# old_line_kick.net
KiCad netlist of a schematic drawn in EAGLE
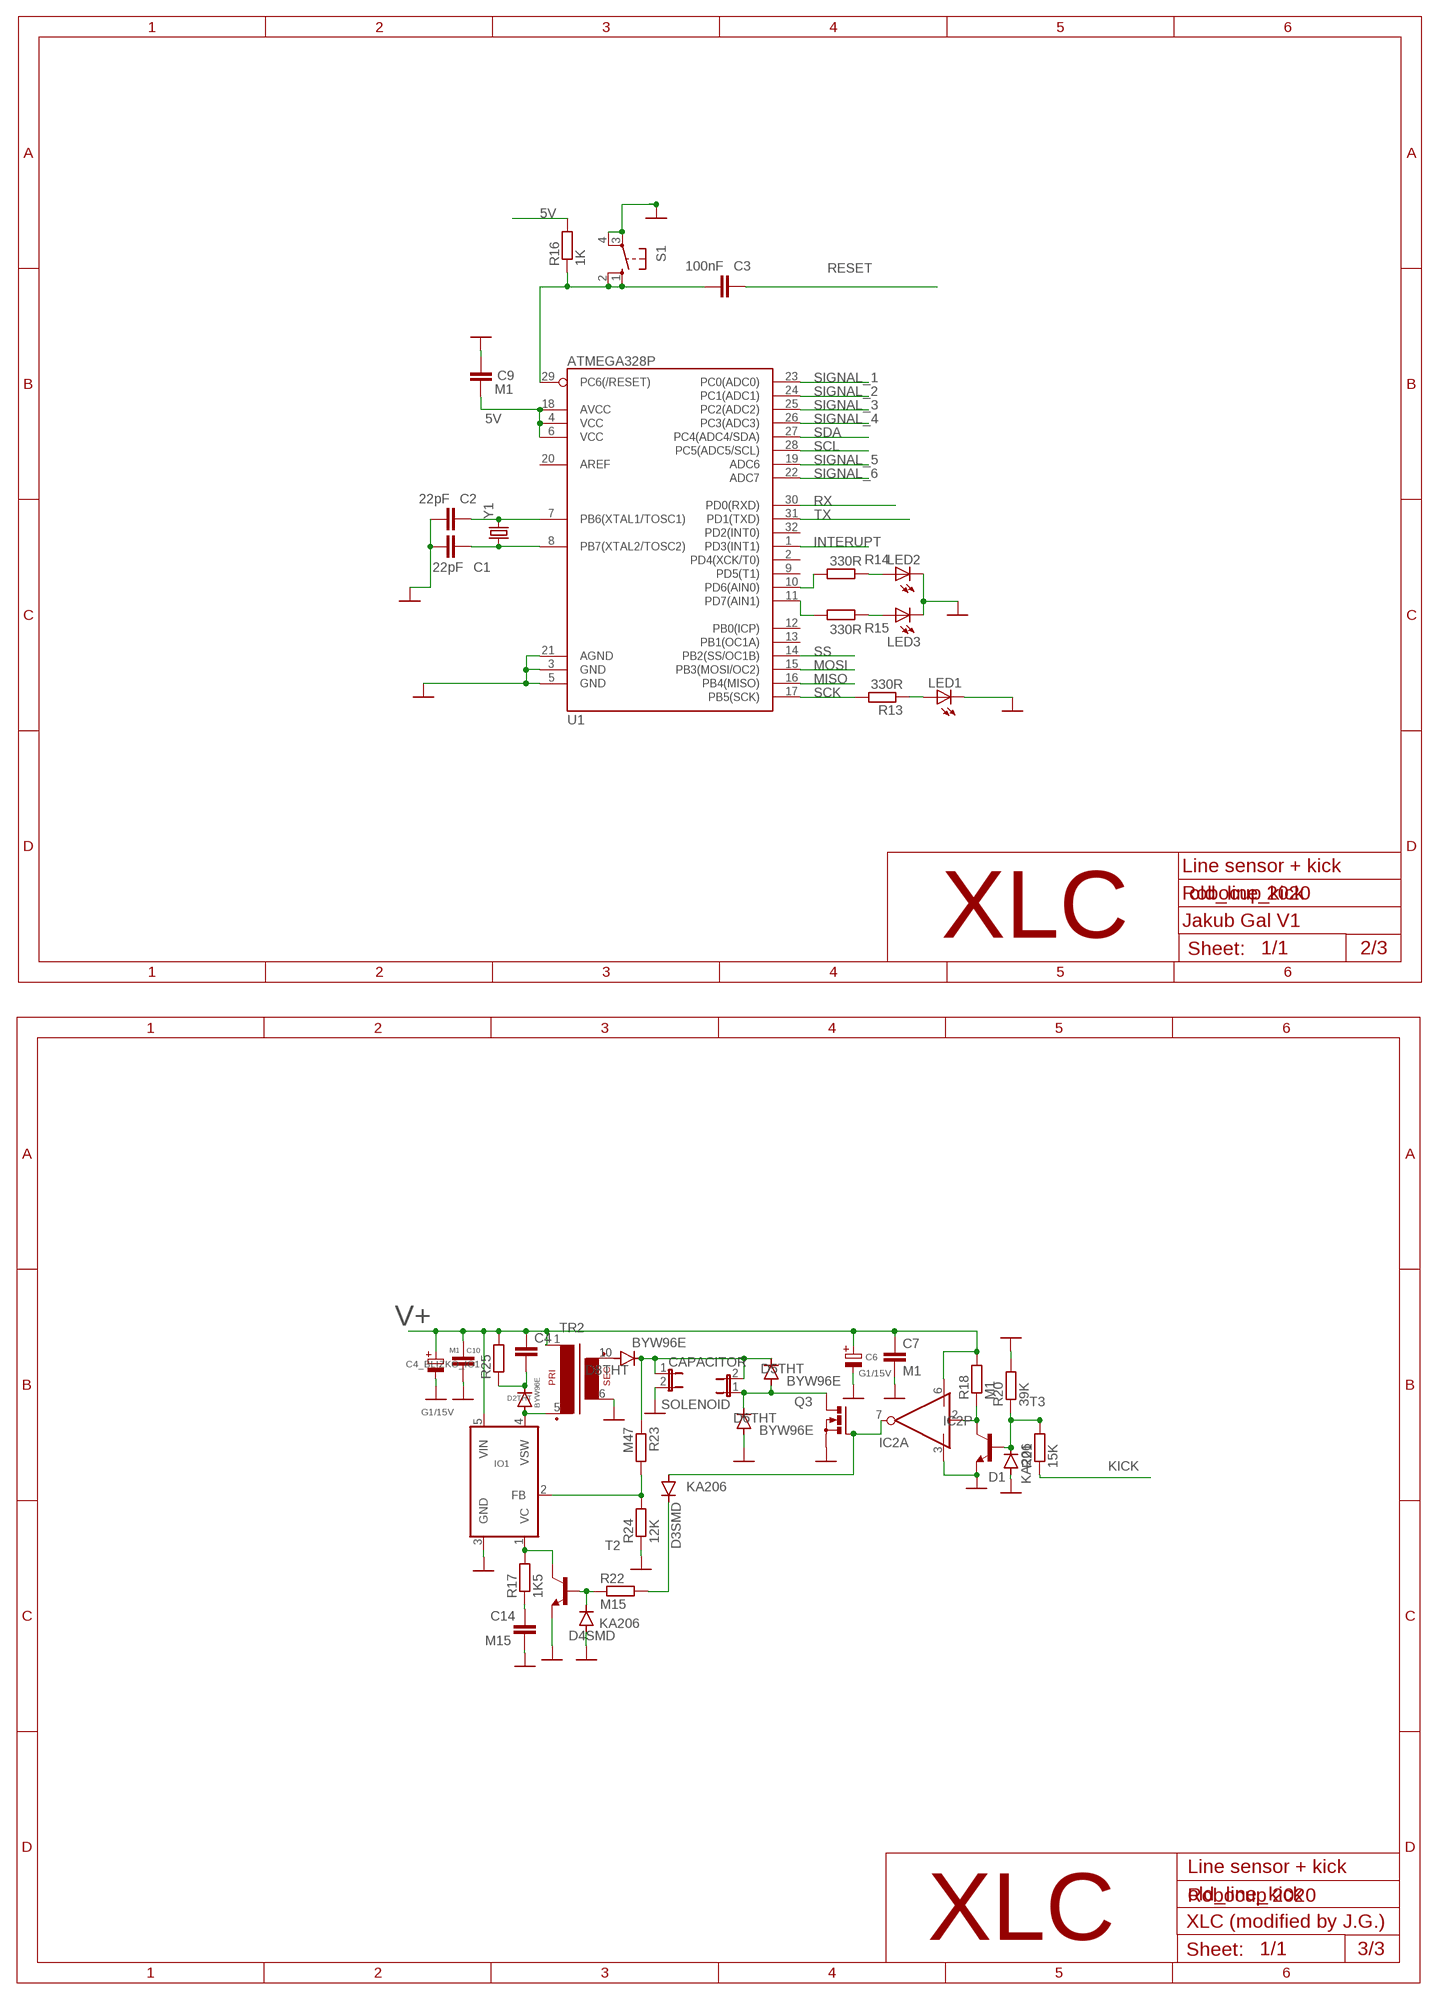
[diagram p0: schematic, sheet 1, part 1 of 2]
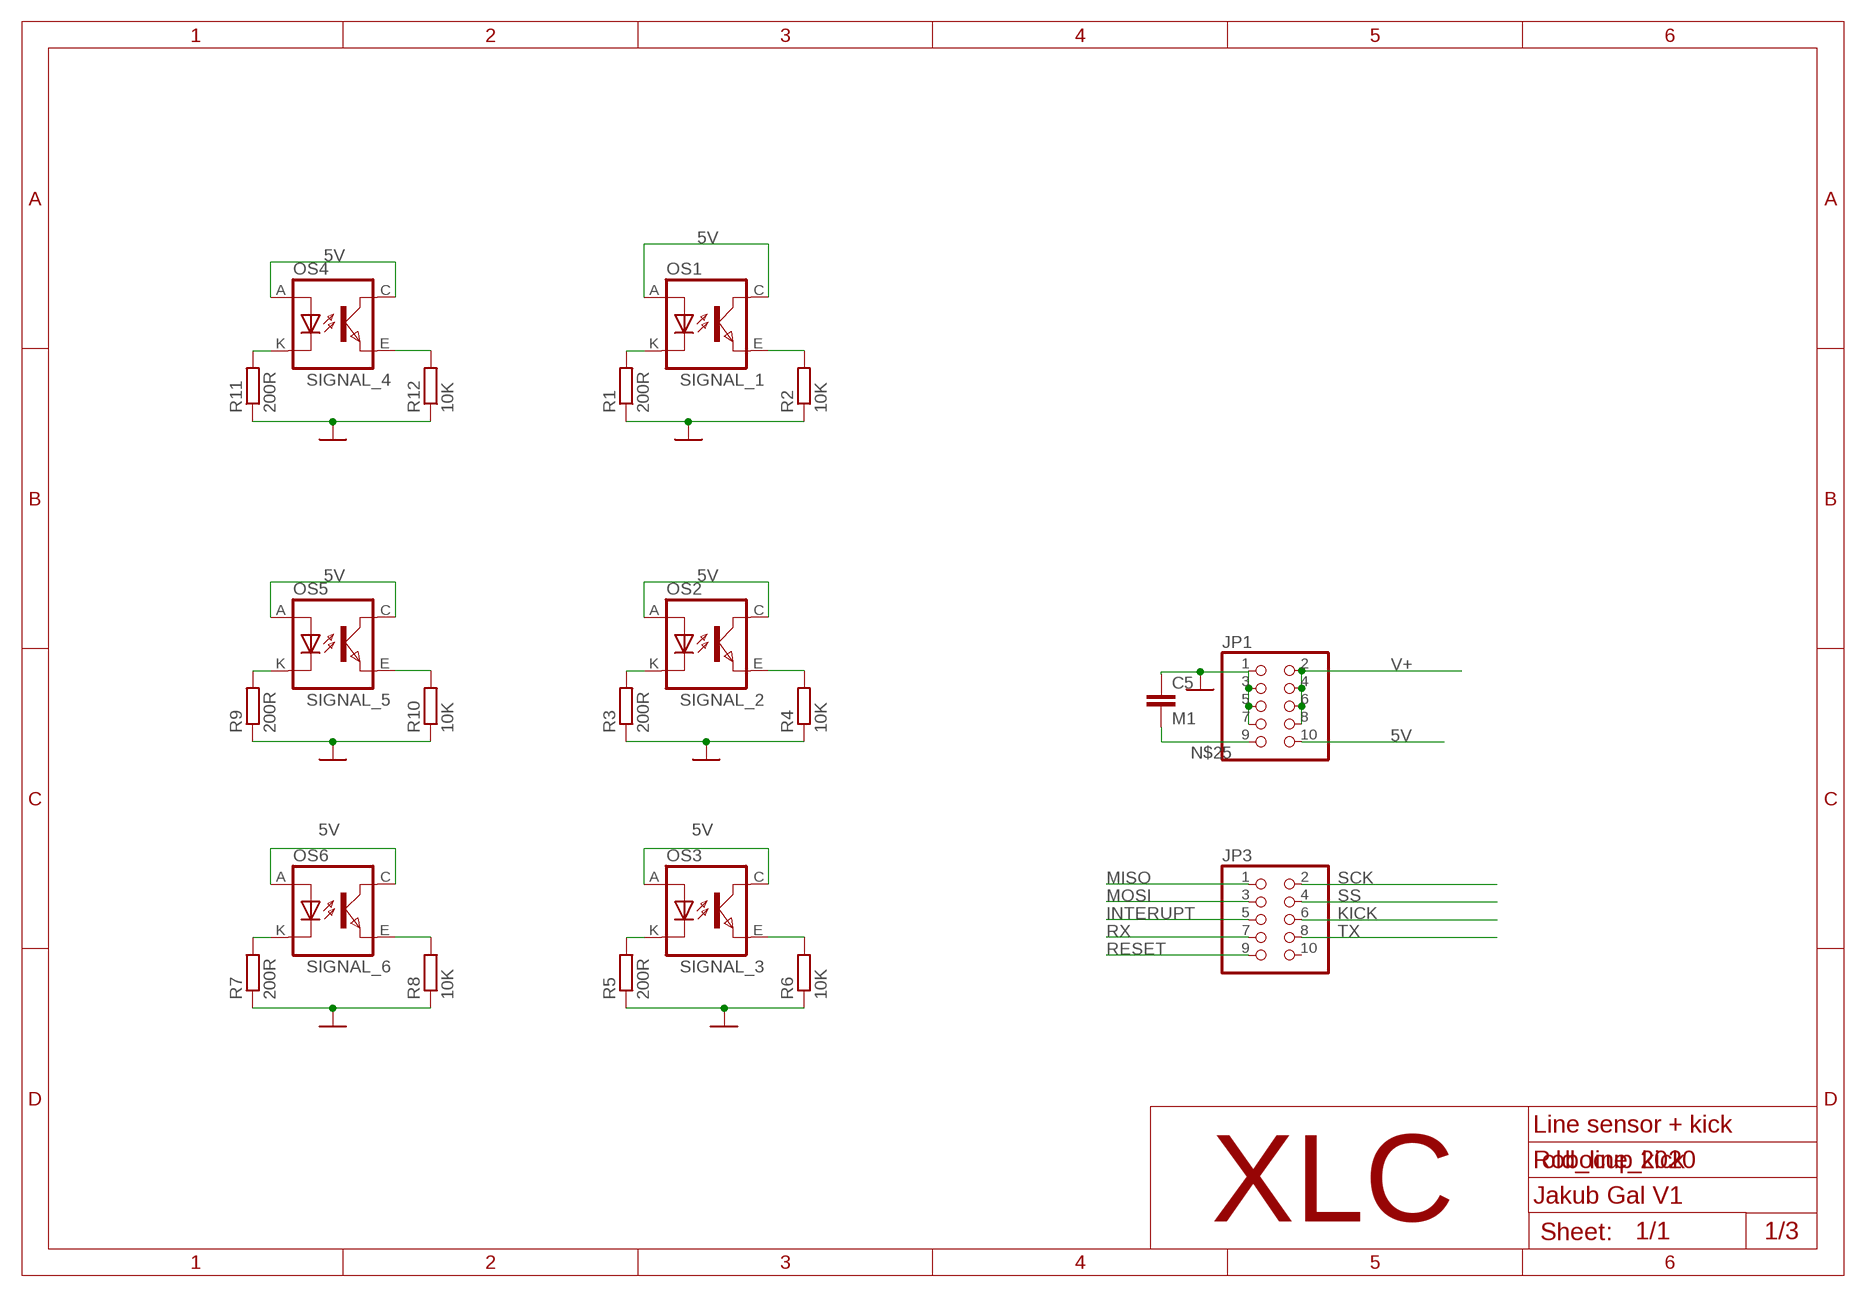
[diagram p1: schematic, sheet 1, part 2 of 2]

(export (version "E")
  (design (tool "Eeschema 10.0.6"))
  (components
    (comp (ref "C1")
      (value "22pF")
      (footprint "eagle-import:C0603")
      (libsource (lib "eagle-import") (part "rcl@1_C-EUC0603"))
    )
    (comp (ref "C2")
      (value "22pF")
      (footprint "eagle-import:C0603")
      (libsource (lib "eagle-import") (part "rcl@1_C-EUC0603"))
    )
    (comp (ref "C3")
      (value "100nF")
      (footprint "eagle-import:C0603")
      (libsource (lib "eagle-import") (part "rcl@1_C-EUC0603"))
    )
    (comp (ref "C4")
      (value "C-EU075-052X106")
      (footprint "eagle-import:C075-052X106")
      (libsource (lib "eagle-import") (part "C-EU075-052X106"))
    )
    (comp (ref "C4_BLIZKO_IO1")
      (value "G1/15V")
      (footprint "eagle-import:E-2,5_7-RAD")
      (libsource (lib "eagle-import") (part "KOND-ELEKT-2,5/7"))
    )
    (comp (ref "C5")
      (value "M1")
      (footprint "eagle-import:C0603")
      (libsource (lib "eagle-import") (part "C-EUC0603"))
    )
    (comp (ref "C6")
      (value "G1/15V")
      (footprint "eagle-import:E-2,5_7-RAD")
      (libsource (lib "eagle-import") (part "KOND-ELEKT-2,5/7"))
    )
    (comp (ref "C7")
      (value "M1")
      (footprint "eagle-import:C0805K")
      (libsource (lib "eagle-import") (part "resistor_C-EUC0805K"))
    )
    (comp (ref "C9")
      (value "M1")
      (footprint "eagle-import:C0603")
      (libsource (lib "eagle-import") (part "rcl@1_C-EUC0603"))
    )
    (comp (ref "C10")
      (value "M1")
      (footprint "eagle-import:C0805K")
      (libsource (lib "eagle-import") (part "resistor_C-EUC0805K"))
    )
    (comp (ref "C14")
      (value "M15")
      (footprint "eagle-import:C0805K")
      (libsource (lib "eagle-import") (part "resistor_C-EUC0805K"))
    )
    (comp (ref "CAPACITOR")
      (value "JP1E")
      (footprint "eagle-import:JP1")
      (libsource (lib "eagle-import") (part "JP1E"))
    )
    (comp (ref "D1")
      (value "KA206")
      (footprint "eagle-import:D-7.5")
      (libsource (lib "eagle-import") (part "DIODE-D-7.5"))
    )
    (comp (ref "D2THT")
      (value "BYW96E")
      (footprint "eagle-import:SOD64-10")
      (libsource (lib "eagle-import") (part "BYW96"))
    )
    (comp (ref "D3SMD")
      (value "KA206")
      (footprint "eagle-import:D-7.5")
      (libsource (lib "eagle-import") (part "DIODE-D-7.5"))
    )
    (comp (ref "D4SMD")
      (value "KA206")
      (footprint "eagle-import:D-7.5")
      (libsource (lib "eagle-import") (part "DIODE-D-7.5"))
    )
    (comp (ref "D5THT")
      (value "BYW96E")
      (footprint "eagle-import:SOD64-10")
      (libsource (lib "eagle-import") (part "BYW96"))
    )
    (comp (ref "D6THT")
      (value "BYW96E")
      (footprint "eagle-import:SOD64-10")
      (libsource (lib "eagle-import") (part "BYW96"))
    )
    (comp (ref "D8THT")
      (value "BYW96E")
      (footprint "eagle-import:SOD64-10")
      (libsource (lib "eagle-import") (part "BYW96"))
    )
    (comp (ref "IC2")
      (value "MIC4423BM")
      (footprint "eagle-import:SO08")
      (libsource (lib "eagle-import") (part "MIC4423BM"))
    )
    (comp (ref "IO1")
      (value "LT1071V")
      (footprint "eagle-import:TO220-5P")
      (libsource (lib "eagle-import") (part "LT1071V"))
    )
    (comp (ref "JP1")
      (value "PINHD-2X5IDC")
      (footprint "eagle-import:2X05_IDC")
      (libsource (lib "eagle-import") (part "PINHD-2X5IDC"))
    )
    (comp (ref "JP3")
      (value "PINHD-2X5IDC")
      (footprint "eagle-import:2X05_IDC")
      (libsource (lib "eagle-import") (part "PINHD-2X5IDC"))
    )
    (comp (ref "LED1")
      (value "LEDCHIPLED_0603")
      (footprint "eagle-import:CHIPLED_0603")
      (libsource (lib "eagle-import") (part "LEDCHIPLED_0603"))
    )
    (comp (ref "LED2")
      (value "LEDCHIPLED_0603")
      (footprint "eagle-import:CHIPLED_0603")
      (libsource (lib "eagle-import") (part "LEDCHIPLED_0603"))
    )
    (comp (ref "LED3")
      (value "LEDCHIPLED_0603")
      (footprint "eagle-import:CHIPLED_0603")
      (libsource (lib "eagle-import") (part "LEDCHIPLED_0603"))
    )
    (comp (ref "OS1")
      (value "TCRT5000")
      (footprint "eagle-import:TCRT5000")
      (libsource (lib "eagle-import") (part "TCRT5000"))
    )
    (comp (ref "OS2")
      (value "TCRT5000")
      (footprint "eagle-import:TCRT5000")
      (libsource (lib "eagle-import") (part "TCRT5000"))
    )
    (comp (ref "OS3")
      (value "TCRT5000")
      (footprint "eagle-import:TCRT5000")
      (libsource (lib "eagle-import") (part "TCRT5000"))
    )
    (comp (ref "OS4")
      (value "TCRT5000")
      (footprint "eagle-import:TCRT5000")
      (fields (field (name "SPICEPREFIX") "O"))
      (libsource (lib "eagle-import") (part "TCRT5000"))
    )
    (comp (ref "OS5")
      (value "TCRT5000")
      (footprint "eagle-import:TCRT5000")
      (libsource (lib "eagle-import") (part "TCRT5000"))
    )
    (comp (ref "OS6")
      (value "TCRT5000")
      (footprint "eagle-import:TCRT5000")
      (fields (field (name "SPICEPREFIX") "O"))
      (libsource (lib "eagle-import") (part "TCRT5000"))
    )
    (comp (ref "Q3")
      (value "PMOSFET_NTO220BV")
      (footprint "eagle-import:TO220BV")
      (libsource (lib "eagle-import") (part "PMOSFET_NTO220BV"))
    )
    (comp (ref "R1")
      (value "200R")
      (footprint "eagle-import:R0603")
      (libsource (lib "eagle-import") (part "R-EU_R0603"))
    )
    (comp (ref "R2")
      (value "10K")
      (footprint "eagle-import:R0603")
      (libsource (lib "eagle-import") (part "R-EU_R0603"))
    )
    (comp (ref "R3")
      (value "200R")
      (footprint "eagle-import:R0603")
      (libsource (lib "eagle-import") (part "R-EU_R0603"))
    )
    (comp (ref "R4")
      (value "10K")
      (footprint "eagle-import:R0603")
      (libsource (lib "eagle-import") (part "R-EU_R0603"))
    )
    (comp (ref "R5")
      (value "200R")
      (footprint "eagle-import:R0603")
      (libsource (lib "eagle-import") (part "R-EU_R0603"))
    )
    (comp (ref "R6")
      (value "10K")
      (footprint "eagle-import:R0603")
      (libsource (lib "eagle-import") (part "R-EU_R0603"))
    )
    (comp (ref "R7")
      (value "200R")
      (footprint "eagle-import:R0603")
      (libsource (lib "eagle-import") (part "R-EU_R0603"))
    )
    (comp (ref "R8")
      (value "10K")
      (footprint "eagle-import:R0603")
      (libsource (lib "eagle-import") (part "R-EU_R0603"))
    )
    (comp (ref "R9")
      (value "200R")
      (footprint "eagle-import:R0603")
      (libsource (lib "eagle-import") (part "R-EU_R0603"))
    )
    (comp (ref "R10")
      (value "10K")
      (footprint "eagle-import:R0603")
      (libsource (lib "eagle-import") (part "R-EU_R0603"))
    )
    (comp (ref "R11")
      (value "200R")
      (footprint "eagle-import:R0603")
      (libsource (lib "eagle-import") (part "R-EU_R0603"))
    )
    (comp (ref "R12")
      (value "10K")
      (footprint "eagle-import:R0603")
      (libsource (lib "eagle-import") (part "R-EU_R0603"))
    )
    (comp (ref "R13")
      (value "330R")
      (footprint "eagle-import:R0603")
      (libsource (lib "eagle-import") (part "R-EU_R0603"))
    )
    (comp (ref "R14")
      (value "330R")
      (footprint "eagle-import:R0603")
      (libsource (lib "eagle-import") (part "R-EU_R0603"))
    )
    (comp (ref "R15")
      (value "330R")
      (footprint "eagle-import:R0603")
      (libsource (lib "eagle-import") (part "R-EU_R0603"))
    )
    (comp (ref "R16")
      (value "1K")
      (footprint "eagle-import:R0603")
      (libsource (lib "eagle-import") (part "R-EU_R0603"))
    )
    (comp (ref "R17")
      (value "1K5")
      (footprint "eagle-import:R1206")
      (libsource (lib "eagle-import") (part "R-EU_R1206"))
    )
    (comp (ref "R18")
      (value "M1")
      (footprint "eagle-import:R1206")
      (libsource (lib "eagle-import") (part "R-EU_R1206"))
    )
    (comp (ref "R20")
      (value "39K")
      (footprint "eagle-import:R1206")
      (libsource (lib "eagle-import") (part "R-EU_R1206"))
    )
    (comp (ref "R21")
      (value "15K")
      (footprint "eagle-import:R1206")
      (libsource (lib "eagle-import") (part "R-EU_R1206"))
    )
    (comp (ref "R22")
      (value "M15")
      (footprint "eagle-import:R1206")
      (libsource (lib "eagle-import") (part "R-EU_R1206"))
    )
    (comp (ref "R23")
      (value "M47")
      (footprint "eagle-import:R1206")
      (libsource (lib "eagle-import") (part "R-EU_R1206"))
    )
    (comp (ref "R24")
      (value "12K")
      (footprint "eagle-import:R1206")
      (libsource (lib "eagle-import") (part "R-EU_R1206"))
    )
    (comp (ref "R25")
      (value "REZISTOR-7,5MM-HORIZ")
      (footprint "eagle-import:R-7,5H")
      (libsource (lib "eagle-import") (part "REZISTOR-7,5MM-HORIZ"))
    )
    (comp (ref "S1")
      (value "10-XX")
      (footprint "eagle-import:B3F-10XX")
      (fields (field (name "MPN") "B3F-1000"))
      (libsource (lib "eagle-import") (part "10-XX"))
    )
    (comp (ref "SOLENOID")
      (value "JP1E")
      (footprint "eagle-import:JP1")
      (libsource (lib "eagle-import") (part "JP1E"))
    )
    (comp (ref "T2")
      (value "-NPN-SC59-BEC")
      (footprint "eagle-import:SC59-BEC")
      (libsource (lib "eagle-import") (part "-NPN-SC59-BEC"))
    )
    (comp (ref "T3")
      (value "-NPN-SC59-BEC")
      (footprint "eagle-import:SC59-BEC")
      (libsource (lib "eagle-import") (part "-NPN-SC59-BEC"))
    )
    (comp (ref "TR2")
      (value "TRAFO-E10-R\"\"")
      (footprint "eagle-import:TRAFO-EE17X20")
      (libsource (lib "eagle-import") (part "TRAFO-E10-R{dblquote}{dblquote}"))
    )
    (comp (ref "U1")
      (value "ATMEGA328P")
      (footprint "eagle-import:TQFP32-08")
      (libsource (lib "eagle-import") (part "ATMEGA328_SMT"))
    )
    (comp (ref "Y1")
      (value "CRYSTALHC49US")
      (footprint "eagle-import:HC49US")
      (libsource (lib "eagle-import") (part "CRYSTALHC49US"))
    )
  )
  (nets
    (net (code "1") (name "/5V") (class "Default")
      (node (ref "C9") (pin "1") (pinfunction "1_1") (pintype "passive"))
      (node (ref "JP1") (pin "10") (pinfunction "10_10") (pintype "passive"))
      (node (ref "OS1") (pin "A") (pinfunction "ANODE_A") (pintype "passive"))
      (node (ref "OS1") (pin "C") (pinfunction "COLLECTOR_C") (pintype "passive"))
      (node (ref "OS2") (pin "A") (pinfunction "ANODE_A") (pintype "passive"))
      (node (ref "OS2") (pin "C") (pinfunction "COLLECTOR_C") (pintype "passive"))
      (node (ref "OS3") (pin "A") (pinfunction "ANODE_A") (pintype "passive"))
      (node (ref "OS3") (pin "C") (pinfunction "COLLECTOR_C") (pintype "passive"))
      (node (ref "OS4") (pin "A") (pinfunction "ANODE_A") (pintype "passive"))
      (node (ref "OS4") (pin "C") (pinfunction "COLLECTOR_C") (pintype "passive"))
      (node (ref "OS5") (pin "A") (pinfunction "ANODE_A") (pintype "passive"))
      (node (ref "OS5") (pin "C") (pinfunction "COLLECTOR_C") (pintype "passive"))
      (node (ref "OS6") (pin "A") (pinfunction "ANODE_A") (pintype "passive"))
      (node (ref "OS6") (pin "C") (pinfunction "COLLECTOR_C") (pintype "passive"))
      (node (ref "R16") (pin "2") (pinfunction "2_2") (pintype "passive"))
      (node (ref "U1") (pin "18") (pinfunction "AVCC_18") (pintype "bidirectional"))
      (node (ref "U1") (pin "4") (pinfunction "VCC_4") (pintype "bidirectional"))
      (node (ref "U1") (pin "6") (pinfunction "VCC_6") (pintype "bidirectional"))
    )
    (net (code "2") (name "/INTERUPT") (class "Default")
      (node (ref "JP3") (pin "5") (pinfunction "5_5") (pintype "passive"))
      (node (ref "U1") (pin "1") (pinfunction "PD3(INT1)_1") (pintype "bidirectional"))
    )
    (net (code "3") (name "/KICK") (class "Default")
      (node (ref "JP3") (pin "6") (pinfunction "6_6") (pintype "passive"))
      (node (ref "R21") (pin "1") (pinfunction "1_1") (pintype "passive"))
    )
    (net (code "4") (name "/MISO") (class "Default")
      (node (ref "JP3") (pin "1") (pinfunction "1_1") (pintype "passive"))
      (node (ref "U1") (pin "16") (pinfunction "PB4(MISO)_16") (pintype "bidirectional"))
    )
    (net (code "5") (name "/MOSI") (class "Default")
      (node (ref "JP3") (pin "3") (pinfunction "3_3") (pintype "passive"))
      (node (ref "U1") (pin "15") (pinfunction "PB3(MOSI/OC2)_15") (pintype "bidirectional"))
    )
    (net (code "6") (name "/N$25") (class "Default")
      (node (ref "C5") (pin "2") (pinfunction "2_2") (pintype "passive"))
      (node (ref "JP1") (pin "9") (pinfunction "9_9") (pintype "passive"))
    )
    (net (code "7") (name "/RESET") (class "Default")
      (node (ref "C3") (pin "2") (pinfunction "2_2") (pintype "passive"))
      (node (ref "JP3") (pin "9") (pinfunction "9_9") (pintype "passive"))
    )
    (net (code "8") (name "/RX") (class "Default")
      (node (ref "JP3") (pin "7") (pinfunction "7_7") (pintype "passive"))
      (node (ref "U1") (pin "30") (pinfunction "PD0(RXD)_30") (pintype "bidirectional"))
    )
    (net (code "9") (name "/SCK") (class "Default")
      (node (ref "JP3") (pin "2") (pinfunction "2_2") (pintype "passive"))
      (node (ref "R13") (pin "2") (pinfunction "2_2") (pintype "passive"))
      (node (ref "U1") (pin "17") (pinfunction "PB5(SCK)_17") (pintype "bidirectional"))
    )
    (net (code "10") (name "/SCL") (class "Default")
      (node (ref "U1") (pin "28") (pinfunction "PC5(ADC5/SCL)_28") (pintype "bidirectional"))
    )
    (net (code "11") (name "/SDA") (class "Default")
      (node (ref "U1") (pin "27") (pinfunction "PC4(ADC4/SDA)_27") (pintype "bidirectional"))
    )
    (net (code "12") (name "/SIGNAL_1") (class "Default")
      (node (ref "OS1") (pin "E") (pinfunction "EMITTER_E") (pintype "passive"))
      (node (ref "R2") (pin "2") (pinfunction "2_2") (pintype "passive"))
      (node (ref "U1") (pin "23") (pinfunction "PC0(ADC0)_23") (pintype "bidirectional"))
    )
    (net (code "13") (name "/SIGNAL_2") (class "Default")
      (node (ref "OS2") (pin "E") (pinfunction "EMITTER_E") (pintype "passive"))
      (node (ref "R4") (pin "2") (pinfunction "2_2") (pintype "passive"))
      (node (ref "U1") (pin "24") (pinfunction "PC1(ADC1)_24") (pintype "bidirectional"))
    )
    (net (code "14") (name "/SIGNAL_3") (class "Default")
      (node (ref "OS3") (pin "E") (pinfunction "EMITTER_E") (pintype "passive"))
      (node (ref "R6") (pin "2") (pinfunction "2_2") (pintype "passive"))
      (node (ref "U1") (pin "25") (pinfunction "PC2(ADC2)_25") (pintype "bidirectional"))
    )
    (net (code "15") (name "/SIGNAL_4") (class "Default")
      (node (ref "OS4") (pin "E") (pinfunction "EMITTER_E") (pintype "passive"))
      (node (ref "R12") (pin "2") (pinfunction "2_2") (pintype "passive"))
      (node (ref "U1") (pin "26") (pinfunction "PC3(ADC3)_26") (pintype "bidirectional"))
    )
    (net (code "16") (name "/SIGNAL_5") (class "Default")
      (node (ref "OS5") (pin "E") (pinfunction "EMITTER_E") (pintype "passive"))
      (node (ref "R10") (pin "2") (pinfunction "2_2") (pintype "passive"))
      (node (ref "U1") (pin "19") (pinfunction "ADC6_19") (pintype "bidirectional"))
    )
    (net (code "17") (name "/SIGNAL_6") (class "Default")
      (node (ref "OS6") (pin "E") (pinfunction "EMITTER_E") (pintype "passive"))
      (node (ref "R8") (pin "2") (pinfunction "2_2") (pintype "passive"))
      (node (ref "U1") (pin "22") (pinfunction "ADC7_22") (pintype "bidirectional"))
    )
    (net (code "18") (name "/SS") (class "Default")
      (node (ref "JP3") (pin "4") (pinfunction "4_4") (pintype "passive"))
      (node (ref "U1") (pin "14") (pinfunction "PB2(SS/OC1B)_14") (pintype "bidirectional"))
    )
    (net (code "19") (name "/TX") (class "Default")
      (node (ref "JP3") (pin "8") (pinfunction "8_8") (pintype "passive"))
      (node (ref "U1") (pin "31") (pinfunction "PD1(TXD)_31") (pintype "bidirectional"))
    )
    (net (code "20") (name "/V+") (class "Default")
      (node (ref "C10") (pin "1") (pinfunction "1_1") (pintype "passive"))
      (node (ref "C4") (pin "1") (pinfunction "1_1") (pintype "passive"))
      (node (ref "C4_BLIZKO_IO1") (pin "+") (pinfunction "+_+") (pintype "passive"))
      (node (ref "C6") (pin "+") (pinfunction "+_+") (pintype "passive"))
      (node (ref "C7") (pin "1") (pinfunction "1_1") (pintype "passive"))
      (node (ref "IC2") (pin "6") (pinfunction "V+_6") (pintype "power_in"))
      (node (ref "IO1") (pin "5") (pinfunction "VIN_5") (pintype "power_in"))
      (node (ref "JP1") (pin "2") (pinfunction "2_2") (pintype "passive"))
      (node (ref "JP1") (pin "4") (pinfunction "4_4") (pintype "passive"))
      (node (ref "JP1") (pin "6") (pinfunction "6_6") (pintype "passive"))
      (node (ref "JP1") (pin "8") (pinfunction "8_8") (pintype "passive"))
      (node (ref "R18") (pin "2") (pinfunction "2_2") (pintype "passive"))
      (node (ref "R25") (pin "2") (pinfunction "2_2") (pintype "passive"))
      (node (ref "TR2") (pin "1") (pinfunction "1_1") (pintype "passive"))
    )
    (net (code "21") (name "GND") (class "Default")
      (node (ref "C1") (pin "1") (pinfunction "1_1") (pintype "passive"))
      (node (ref "C10") (pin "2") (pinfunction "2_2") (pintype "passive"))
      (node (ref "C14") (pin "2") (pinfunction "2_2") (pintype "passive"))
      (node (ref "C2") (pin "1") (pinfunction "1_1") (pintype "passive"))
      (node (ref "C4_BLIZKO_IO1") (pin "-") (pinfunction "-_-") (pintype "passive"))
      (node (ref "C5") (pin "1") (pinfunction "1_1") (pintype "passive"))
      (node (ref "C6") (pin "-") (pinfunction "-_-") (pintype "passive"))
      (node (ref "C7") (pin "2") (pinfunction "2_2") (pintype "passive"))
      (node (ref "C9") (pin "2") (pinfunction "2_2") (pintype "passive"))
      (node (ref "CAPACITOR") (pin "2") (pinfunction "2_2") (pintype "passive"))
      (node (ref "D1") (pin "A") (pinfunction "A_A") (pintype "passive"))
      (node (ref "D4SMD") (pin "A") (pinfunction "A_A") (pintype "passive"))
      (node (ref "D6THT") (pin "A") (pinfunction "A_A") (pintype "passive"))
      (node (ref "IC2") (pin "3") (pinfunction "GND_3") (pintype "power_in"))
      (node (ref "IO1") (pin "3") (pinfunction "GND_3") (pintype "power_in"))
      (node (ref "JP1") (pin "1") (pinfunction "1_1") (pintype "passive"))
      (node (ref "JP1") (pin "3") (pinfunction "3_3") (pintype "passive"))
      (node (ref "JP1") (pin "5") (pinfunction "5_5") (pintype "passive"))
      (node (ref "JP1") (pin "7") (pinfunction "7_7") (pintype "passive"))
      (node (ref "LED1") (pin "C") (pinfunction "C_C") (pintype "passive"))
      (node (ref "LED2") (pin "C") (pinfunction "C_C") (pintype "passive"))
      (node (ref "LED3") (pin "C") (pinfunction "C_C") (pintype "passive"))
      (node (ref "Q3") (pin "S") (pinfunction "S_S") (pintype "passive"))
      (node (ref "R1") (pin "1") (pinfunction "1_1") (pintype "passive"))
      (node (ref "R10") (pin "1") (pinfunction "1_1") (pintype "passive"))
      (node (ref "R11") (pin "1") (pinfunction "1_1") (pintype "passive"))
      (node (ref "R12") (pin "1") (pinfunction "1_1") (pintype "passive"))
      (node (ref "R2") (pin "1") (pinfunction "1_1") (pintype "passive"))
      (node (ref "R20") (pin "2") (pinfunction "2_2") (pintype "passive"))
      (node (ref "R24") (pin "1") (pinfunction "1_1") (pintype "passive"))
      (node (ref "R3") (pin "1") (pinfunction "1_1") (pintype "passive"))
      (node (ref "R4") (pin "1") (pinfunction "1_1") (pintype "passive"))
      (node (ref "R5") (pin "1") (pinfunction "1_1") (pintype "passive"))
      (node (ref "R6") (pin "1") (pinfunction "1_1") (pintype "passive"))
      (node (ref "R7") (pin "1") (pinfunction "1_1") (pintype "passive"))
      (node (ref "R8") (pin "1") (pinfunction "1_1") (pintype "passive"))
      (node (ref "R9") (pin "1") (pinfunction "1_1") (pintype "passive"))
      (node (ref "S1") (pin "3") (pinfunction "P_3") (pintype "passive"))
      (node (ref "S1") (pin "4") (pinfunction "P1_4") (pintype "passive"))
      (node (ref "T2") (pin "E") (pinfunction "E_E") (pintype "passive"))
      (node (ref "T3") (pin "E") (pinfunction "E_E") (pintype "passive"))
      (node (ref "TR2") (pin "6") (pinfunction "3_6") (pintype "passive"))
      (node (ref "U1") (pin "21") (pinfunction "AGND_21") (pintype "bidirectional"))
      (node (ref "U1") (pin "3") (pinfunction "GND_3") (pintype "bidirectional"))
      (node (ref "U1") (pin "5") (pinfunction "GND_5") (pintype "bidirectional"))
    )
    (net (code "22") (name "Net-(C4-Pad2)") (class "Default")
      (node (ref "C4") (pin "2") (pinfunction "2_2") (pintype "passive"))
      (node (ref "D2THT") (pin "C") (pinfunction "C_C") (pintype "passive"))
      (node (ref "R25") (pin "1") (pinfunction "1_1") (pintype "passive"))
    )
    (net (code "23") (name "Net-(C14-Pad1)") (class "Default")
      (node (ref "C14") (pin "1") (pinfunction "1_1") (pintype "passive"))
      (node (ref "R17") (pin "1") (pinfunction "1_1") (pintype "passive"))
    )
    (net (code "24") (name "Net-(CAPACITOR-Pad1)") (class "Default")
      (node (ref "CAPACITOR") (pin "1") (pinfunction "1_1") (pintype "passive"))
      (node (ref "D5THT") (pin "C") (pinfunction "C_C") (pintype "passive"))
      (node (ref "D8THT") (pin "C") (pinfunction "C_C") (pintype "passive"))
      (node (ref "R23") (pin "1") (pinfunction "1_1") (pintype "passive"))
      (node (ref "SOLENOID") (pin "2") (pinfunction "2_2") (pintype "passive"))
    )
    (net (code "25") (name "Net-(D1-PadC)") (class "Default")
      (node (ref "D1") (pin "C") (pinfunction "C_C") (pintype "passive"))
      (node (ref "R20") (pin "1") (pinfunction "1_1") (pintype "passive"))
      (node (ref "R21") (pin "2") (pinfunction "2_2") (pintype "passive"))
      (node (ref "T3") (pin "B") (pinfunction "B_B") (pintype "passive"))
    )
    (net (code "26") (name "Net-(D3SMD-PadC)") (class "Default")
      (node (ref "D3SMD") (pin "C") (pinfunction "C_C") (pintype "passive"))
      (node (ref "R22") (pin "2") (pinfunction "2_2") (pintype "passive"))
    )
    (net (code "27") (name "Net-(D4SMD-PadC)") (class "Default")
      (node (ref "D4SMD") (pin "C") (pinfunction "C_C") (pintype "passive"))
      (node (ref "R22") (pin "1") (pinfunction "1_1") (pintype "passive"))
      (node (ref "T2") (pin "B") (pinfunction "B_B") (pintype "passive"))
    )
    (net (code "28") (name "Net-(D5THT-PadA)") (class "Default")
      (node (ref "D5THT") (pin "A") (pinfunction "A_A") (pintype "passive"))
      (node (ref "D6THT") (pin "C") (pinfunction "C_C") (pintype "passive"))
      (node (ref "Q3") (pin "D") (pinfunction "D_D") (pintype "passive"))
      (node (ref "SOLENOID") (pin "1") (pinfunction "1_1") (pintype "passive"))
    )
    (net (code "29") (name "Net-(IC2A-IN)") (class "Default")
      (node (ref "IC2") (pin "2") (pinfunction "IN_2") (pintype "input"))
      (node (ref "R18") (pin "1") (pinfunction "1_1") (pintype "passive"))
      (node (ref "T3") (pin "C") (pinfunction "C_C") (pintype "passive"))
    )
    (net (code "30") (name "Net-(IC2A-OUT)") (class "Default")
      (node (ref "D3SMD") (pin "A") (pinfunction "A_A") (pintype "passive"))
      (node (ref "IC2") (pin "7") (pinfunction "OUT_7") (pintype "output"))
      (node (ref "Q3") (pin "G") (pinfunction "G_G") (pintype "passive"))
    )
    (net (code "31") (name "Net-(IO1-FB)") (class "Default")
      (node (ref "IO1") (pin "2") (pinfunction "FB_2") (pintype "input"))
      (node (ref "R23") (pin "2") (pinfunction "2_2") (pintype "passive"))
      (node (ref "R24") (pin "2") (pinfunction "2_2") (pintype "passive"))
    )
    (net (code "32") (name "Net-(IO1-VC)") (class "Default")
      (node (ref "IO1") (pin "1") (pinfunction "VC_1") (pintype "input"))
      (node (ref "R17") (pin "2") (pinfunction "2_2") (pintype "passive"))
      (node (ref "T2") (pin "C") (pinfunction "C_C") (pintype "passive"))
    )
    (net (code "33") (name "Net-(IO1-VSW)") (class "Default")
      (node (ref "D2THT") (pin "A") (pinfunction "A_A") (pintype "passive"))
      (node (ref "IO1") (pin "4") (pinfunction "VSW_4") (pintype "output"))
      (node (ref "TR2") (pin "5") (pinfunction "2_5") (pintype "passive"))
    )
    (net (code "34") (name "Net-(LED1-PadA)") (class "Default")
      (node (ref "LED1") (pin "A") (pinfunction "A_A") (pintype "passive"))
      (node (ref "R13") (pin "1") (pinfunction "1_1") (pintype "passive"))
    )
    (net (code "35") (name "Net-(LED2-PadA)") (class "Default")
      (node (ref "LED2") (pin "A") (pinfunction "A_A") (pintype "passive"))
      (node (ref "R14") (pin "1") (pinfunction "1_1") (pintype "passive"))
    )
    (net (code "36") (name "Net-(LED3-PadA)") (class "Default")
      (node (ref "LED3") (pin "A") (pinfunction "A_A") (pintype "passive"))
      (node (ref "R15") (pin "1") (pinfunction "1_1") (pintype "passive"))
    )
    (net (code "37") (name "Net-(OS1-CATHODE)") (class "Default")
      (node (ref "OS1") (pin "K") (pinfunction "CATHODE_K") (pintype "passive"))
      (node (ref "R1") (pin "2") (pinfunction "2_2") (pintype "passive"))
    )
    (net (code "38") (name "Net-(OS2-CATHODE)") (class "Default")
      (node (ref "OS2") (pin "K") (pinfunction "CATHODE_K") (pintype "passive"))
      (node (ref "R3") (pin "2") (pinfunction "2_2") (pintype "passive"))
    )
    (net (code "39") (name "Net-(OS3-CATHODE)") (class "Default")
      (node (ref "OS3") (pin "K") (pinfunction "CATHODE_K") (pintype "passive"))
      (node (ref "R5") (pin "2") (pinfunction "2_2") (pintype "passive"))
    )
    (net (code "40") (name "Net-(OS4-CATHODE)") (class "Default")
      (node (ref "OS4") (pin "K") (pinfunction "CATHODE_K") (pintype "passive"))
      (node (ref "R11") (pin "2") (pinfunction "2_2") (pintype "passive"))
    )
    (net (code "41") (name "Net-(OS5-CATHODE)") (class "Default")
      (node (ref "OS5") (pin "K") (pinfunction "CATHODE_K") (pintype "passive"))
      (node (ref "R9") (pin "2") (pinfunction "2_2") (pintype "passive"))
    )
    (net (code "42") (name "Net-(OS6-CATHODE)") (class "Default")
      (node (ref "OS6") (pin "K") (pinfunction "CATHODE_K") (pintype "passive"))
      (node (ref "R7") (pin "2") (pinfunction "2_2") (pintype "passive"))
    )
    (net (code "43") (name "Net-(S1-S)") (class "Default")
      (node (ref "C3") (pin "1") (pinfunction "1_1") (pintype "passive"))
      (node (ref "R16") (pin "1") (pinfunction "1_1") (pintype "passive"))
      (node (ref "S1") (pin "1") (pinfunction "S_1") (pintype "passive"))
      (node (ref "S1") (pin "2") (pinfunction "S1_2") (pintype "passive"))
      (node (ref "U1") (pin "29") (pinfunction "PC6(/RESET)_29") (pintype "bidirectional"))
    )
    (net (code "44") (name "Net-(TR2-4)") (class "Default")
      (node (ref "D8THT") (pin "A") (pinfunction "A_A") (pintype "passive"))
      (node (ref "TR2") (pin "10") (pinfunction "4_10") (pintype "passive"))
    )
    (net (code "45") (name "Net-(U1-PB6(XTAL1{slash}TOSC1))") (class "Default")
      (node (ref "C2") (pin "2") (pinfunction "2_2") (pintype "passive"))
      (node (ref "U1") (pin "7") (pinfunction "PB6(XTAL1/TOSC1)_7") (pintype "bidirectional"))
      (node (ref "Y1") (pin "2") (pinfunction "2_2") (pintype "passive"))
    )
    (net (code "46") (name "Net-(U1-PB7(XTAL2{slash}TOSC2))") (class "Default")
      (node (ref "C1") (pin "2") (pinfunction "2_2") (pintype "passive"))
      (node (ref "U1") (pin "8") (pinfunction "PB7(XTAL2/TOSC2)_8") (pintype "bidirectional"))
      (node (ref "Y1") (pin "1") (pinfunction "1_1") (pintype "passive"))
    )
    (net (code "47") (name "Net-(U1-PD6(AIN0))") (class "Default")
      (node (ref "R14") (pin "2") (pinfunction "2_2") (pintype "passive"))
      (node (ref "U1") (pin "10") (pinfunction "PD6(AIN0)_10") (pintype "bidirectional"))
    )
    (net (code "48") (name "Net-(U1-PD7(AIN1))") (class "Default")
      (node (ref "R15") (pin "2") (pinfunction "2_2") (pintype "passive"))
      (node (ref "U1") (pin "11") (pinfunction "PD7(AIN1)_11") (pintype "bidirectional"))
    )
    (net (code "49") (name "unconnected-(JP3-Pad10)") (class "Default")
      (node (ref "JP3") (pin "10") (pinfunction "10_10") (pintype "passive"))
    )
    (net (code "50") (name "unconnected-(U1-AREF-Pad20)") (class "Default")
      (node (ref "U1") (pin "20") (pinfunction "AREF_20") (pintype "bidirectional"))
    )
    (net (code "51") (name "unconnected-(U1-PB0(ICP)-Pad12)") (class "Default")
      (node (ref "U1") (pin "12") (pinfunction "PB0(ICP)_12") (pintype "bidirectional"))
    )
    (net (code "52") (name "unconnected-(U1-PB1(OC1A)-Pad13)") (class "Default")
      (node (ref "U1") (pin "13") (pinfunction "PB1(OC1A)_13") (pintype "bidirectional"))
    )
    (net (code "53") (name "unconnected-(U1-PD2(INT0)-Pad32)") (class "Default")
      (node (ref "U1") (pin "32") (pinfunction "PD2(INT0)_32") (pintype "bidirectional"))
    )
    (net (code "54") (name "unconnected-(U1-PD4(XCK{slash}T0)-Pad2)") (class "Default")
      (node (ref "U1") (pin "2") (pinfunction "PD4(XCK/T0)_2") (pintype "bidirectional"))
    )
    (net (code "55") (name "unconnected-(U1-PD5(T1)-Pad9)") (class "Default")
      (node (ref "U1") (pin "9") (pinfunction "PD5(T1)_9") (pintype "bidirectional"))
    )
  )
)
